# vusbtiny.net
KiCad netlist of a schematic drawn in EAGLE
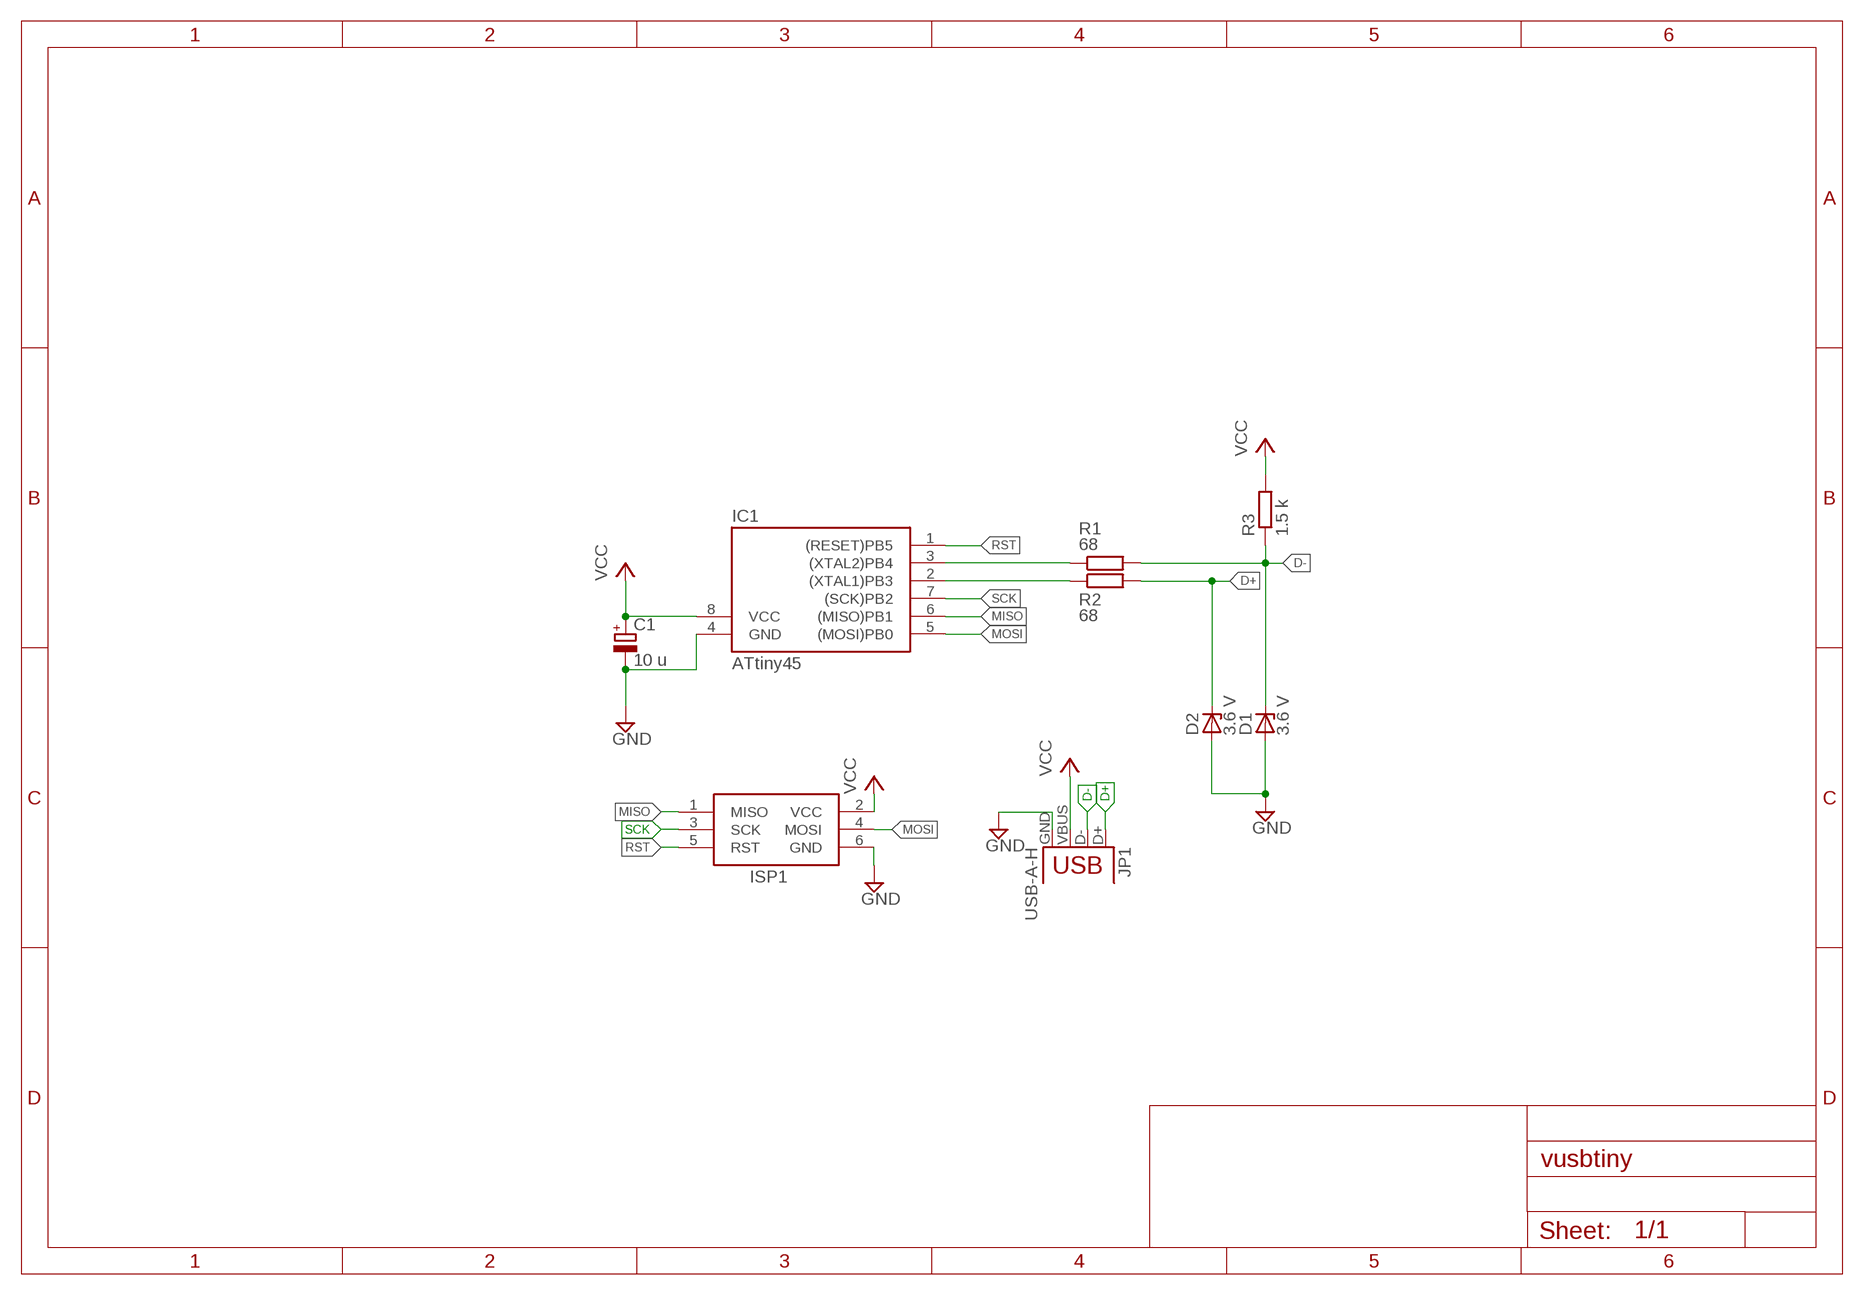
[diagram p0: schematic, sheet 1]

(export (version "E")
  (design (tool "Eeschema 10.0.6"))
  (components
    (comp (ref "C1")
      (value "10 u")
      (footprint "eagle-import:E2,5-5")
      (libsource (lib "eagle-import") (part "CPOL-EUE2.5-5"))
    )
    (comp (ref "D1")
      (value "3.6 V")
      (footprint "eagle-import:DO34Z7")
      (libsource (lib "eagle-import") (part "BZV10"))
    )
    (comp (ref "D2")
      (value "3.6 V")
      (footprint "eagle-import:DO34Z7")
      (libsource (lib "eagle-import") (part "BZV10"))
    )
    (comp (ref "IC1")
      (value "ATtiny45")
      (footprint "eagle-import:DIL08")
      (libsource (lib "eagle-import") (part "TINY12P"))
    )
    (comp (ref "ISP1")
      (value "AVRISP-6")
      (footprint "eagle-import:AVRISP")
      (libsource (lib "eagle-import") (part "AVRISP-6"))
    )
    (comp (ref "JP1")
      (value "USB-A-H")
      (footprint "eagle-import:USB-A-H")
      (libsource (lib "eagle-import") (part "USB-A-H"))
    )
    (comp (ref "R1")
      (value "68")
      (footprint "eagle-import:0207_10")
      (libsource (lib "eagle-import") (part "R-EU_0207/10"))
    )
    (comp (ref "R2")
      (value "68")
      (footprint "eagle-import:0207_10")
      (libsource (lib "eagle-import") (part "R-EU_0207/10"))
    )
    (comp (ref "R3")
      (value "1.5 k")
      (footprint "eagle-import:0207_10")
      (libsource (lib "eagle-import") (part "R-EU_0207/10"))
    )
  )
  (nets
    (net (code "1") (name "D+") (class "Default")
      (node (ref "D2") (pin "C") (pinfunction "C_C") (pintype "passive"))
      (node (ref "JP1") (pin "D+") (pinfunction "D+_D+") (pintype "bidirectional"))
      (node (ref "R2") (pin "2") (pinfunction "2_2") (pintype "passive"))
    )
    (net (code "2") (name "D-") (class "Default")
      (node (ref "D1") (pin "C") (pinfunction "C_C") (pintype "passive"))
      (node (ref "JP1") (pin "D-") (pinfunction "D-_D-") (pintype "bidirectional"))
      (node (ref "R1") (pin "2") (pinfunction "2_2") (pintype "passive"))
      (node (ref "R3") (pin "1") (pinfunction "1_1") (pintype "passive"))
    )
    (net (code "3") (name "GND") (class "Default")
      (node (ref "C1") (pin "-") (pinfunction "-_-") (pintype "passive"))
      (node (ref "D1") (pin "A") (pinfunction "A_A") (pintype "passive"))
      (node (ref "D2") (pin "A") (pinfunction "A_A") (pintype "passive"))
      (node (ref "IC1") (pin "4") (pinfunction "GND_4") (pintype "power_in"))
      (node (ref "ISP1") (pin "6") (pinfunction "GND_6") (pintype "power_in"))
      (node (ref "JP1") (pin "GND") (pinfunction "GND_GND") (pintype "bidirectional"))
    )
    (net (code "4") (name "MISO") (class "Default")
      (node (ref "IC1") (pin "6") (pinfunction "(MISO)PB1_6") (pintype "bidirectional"))
      (node (ref "ISP1") (pin "1") (pinfunction "MISO_1") (pintype "input"))
    )
    (net (code "5") (name "MOSI") (class "Default")
      (node (ref "IC1") (pin "5") (pinfunction "(MOSI)PB0_5") (pintype "bidirectional"))
      (node (ref "ISP1") (pin "4") (pinfunction "MOSI_4") (pintype "output"))
    )
    (net (code "6") (name "Net-(IC1-(XTAL1)PB3)") (class "Default")
      (node (ref "IC1") (pin "2") (pinfunction "(XTAL1)PB3_2") (pintype "bidirectional"))
      (node (ref "R2") (pin "1") (pinfunction "1_1") (pintype "passive"))
    )
    (net (code "7") (name "Net-(IC1-(XTAL2)PB4)") (class "Default")
      (node (ref "IC1") (pin "3") (pinfunction "(XTAL2)PB4_3") (pintype "bidirectional"))
      (node (ref "R1") (pin "1") (pinfunction "1_1") (pintype "passive"))
    )
    (net (code "8") (name "RST") (class "Default")
      (node (ref "IC1") (pin "1") (pinfunction "(RESET)PB5_1") (pintype "bidirectional"))
      (node (ref "ISP1") (pin "5") (pinfunction "RST_5") (pintype "output"))
    )
    (net (code "9") (name "SCK") (class "Default")
      (node (ref "IC1") (pin "7") (pinfunction "(SCK)PB2_7") (pintype "bidirectional"))
      (node (ref "ISP1") (pin "3") (pinfunction "SCK_3") (pintype "output"))
    )
    (net (code "10") (name "VCC") (class "Default")
      (node (ref "C1") (pin "+") (pinfunction "+_+") (pintype "passive"))
      (node (ref "IC1") (pin "8") (pinfunction "VCC_8") (pintype "power_in"))
      (node (ref "ISP1") (pin "2") (pinfunction "VCC_2") (pintype "power_in"))
      (node (ref "JP1") (pin "VBUS") (pinfunction "VBUS_VBUS") (pintype "bidirectional"))
      (node (ref "R3") (pin "2") (pinfunction "2_2") (pintype "passive"))
    )
  )
)
